# mainboard.net
KiCad netlist of a schematic drawn in EAGLE
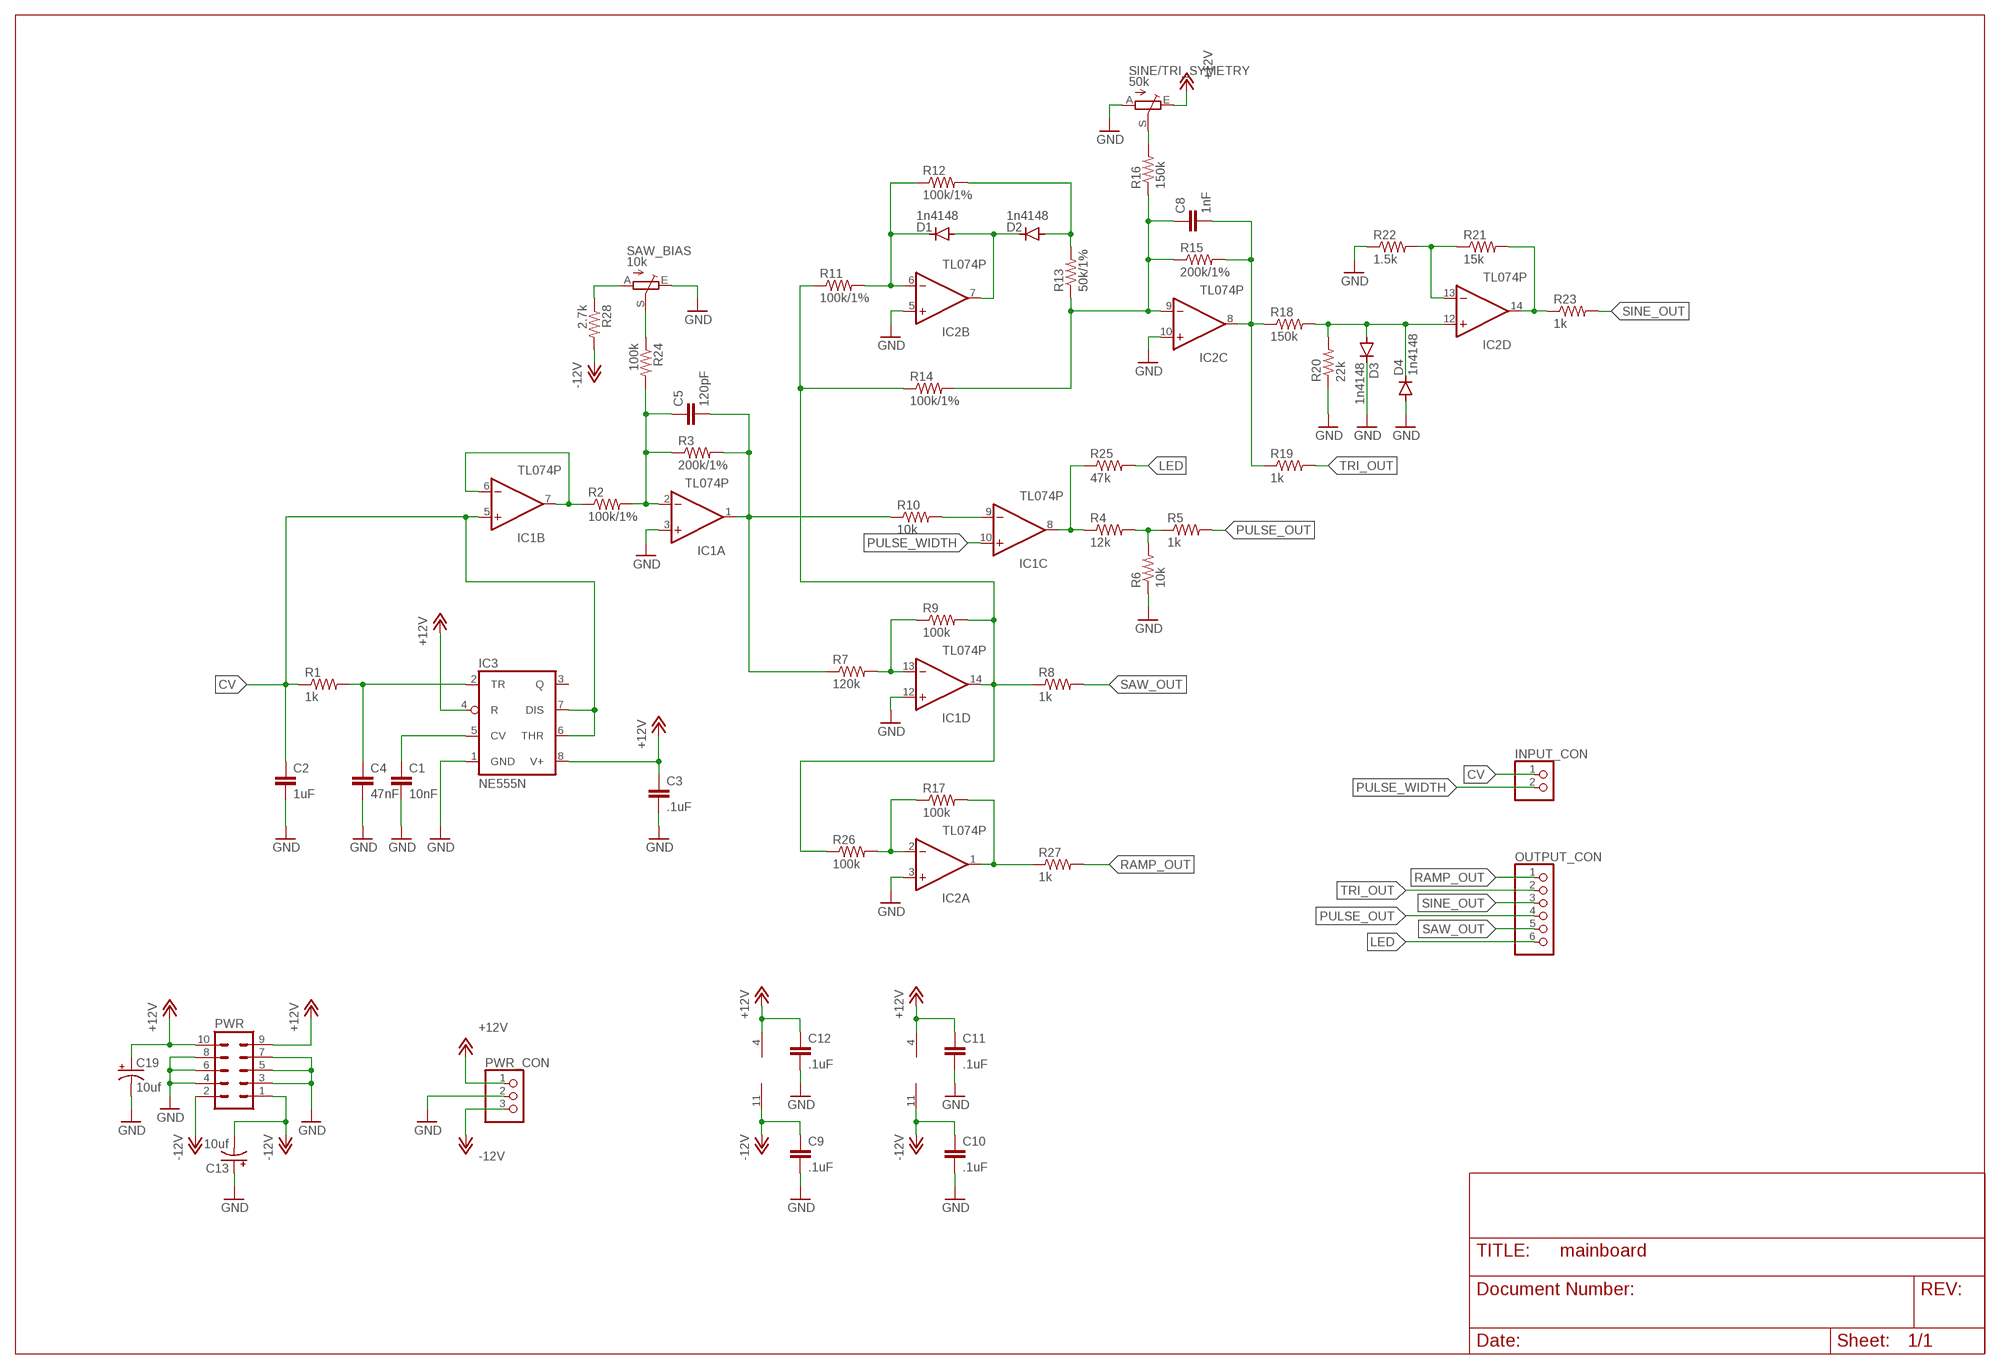
[diagram p0: schematic, sheet 1]

(export (version "E")
  (design (tool "Eeschema 10.0.6"))
  (components
    (comp (ref "C1")
      (value "10nF")
      (footprint "eagle-import:C050-024X044")
      (libsource (lib "eagle-import") (part "C-EU050-024X044"))
    )
    (comp (ref "C2")
      (value "1uF")
      (footprint "eagle-import:C075-032X103")
      (libsource (lib "eagle-import") (part "C-EU075-032X103"))
    )
    (comp (ref "C3")
      (value ".1uF")
      (footprint "eagle-import:C050-024X044")
      (libsource (lib "eagle-import") (part "C-EU050-024X044"))
    )
    (comp (ref "C4")
      (value "47nF")
      (footprint "eagle-import:C050-024X044")
      (libsource (lib "eagle-import") (part "C-EU050-024X044"))
    )
    (comp (ref "C5")
      (value "120pF")
      (footprint "eagle-import:C050-024X044")
      (libsource (lib "eagle-import") (part "C-EU050-024X044"))
    )
    (comp (ref "C8")
      (value "1nF")
      (footprint "eagle-import:C050-024X044")
      (libsource (lib "eagle-import") (part "C-EU050-024X044"))
    )
    (comp (ref "C9")
      (value ".1uF")
      (footprint "eagle-import:C050-024X044")
      (libsource (lib "eagle-import") (part "C-EU050-024X044"))
    )
    (comp (ref "C10")
      (value ".1uF")
      (footprint "eagle-import:C050-024X044")
      (libsource (lib "eagle-import") (part "C-EU050-024X044"))
    )
    (comp (ref "C11")
      (value ".1uF")
      (footprint "eagle-import:C050-024X044")
      (libsource (lib "eagle-import") (part "C-EU050-024X044"))
    )
    (comp (ref "C12")
      (value ".1uF")
      (footprint "eagle-import:C050-024X044")
      (libsource (lib "eagle-import") (part "C-EU050-024X044"))
    )
    (comp (ref "C13")
      (value "10uf")
      (footprint "eagle-import:E2,5-5")
      (libsource (lib "eagle-import") (part "CPOL-USE2.5-5"))
    )
    (comp (ref "C19")
      (value "10uf")
      (footprint "eagle-import:E2,5-5")
      (libsource (lib "eagle-import") (part "CPOL-USE2.5-5"))
    )
    (comp (ref "D1")
      (value "1n4148")
      (footprint "eagle-import:DO35-7")
      (libsource (lib "eagle-import") (part "1N4148DO35-7"))
    )
    (comp (ref "D2")
      (value "1n4148")
      (footprint "eagle-import:DO35-7")
      (libsource (lib "eagle-import") (part "1N4148DO35-7"))
    )
    (comp (ref "D3")
      (value "1n4148")
      (footprint "eagle-import:DO35-7")
      (libsource (lib "eagle-import") (part "1N4148DO35-7"))
    )
    (comp (ref "D4")
      (value "1n4148")
      (footprint "eagle-import:DO35-7")
      (libsource (lib "eagle-import") (part "1N4148DO35-7"))
    )
    (comp (ref "IC1")
      (value "TL074P")
      (footprint "eagle-import:DIL14")
      (libsource (lib "eagle-import") (part "TL074P"))
    )
    (comp (ref "IC2")
      (value "TL074P")
      (footprint "eagle-import:DIL14")
      (libsource (lib "eagle-import") (part "TL074P"))
    )
    (comp (ref "IC3")
      (value "NE555N")
      (footprint "eagle-import:DIL08")
      (libsource (lib "eagle-import") (part "555NNE"))
    )
    (comp (ref "INPUT_CON")
      (value "PINHD-1X2")
      (footprint "eagle-import:1X02")
      (libsource (lib "eagle-import") (part "PINHD-1X2"))
    )
    (comp (ref "OUTPUT_CON")
      (value "PINHD-1X6")
      (footprint "eagle-import:1X06")
      (libsource (lib "eagle-import") (part "PINHD-1X6"))
    )
    (comp (ref "PWR")
      (value "ML10")
      (footprint "eagle-import:ML10")
      (libsource (lib "eagle-import") (part "ML10"))
    )
    (comp (ref "PWR_CON")
      (value "PINHD-1X3")
      (footprint "eagle-import:1X03")
      (libsource (lib "eagle-import") (part "PINHD-1X3"))
    )
    (comp (ref "R1")
      (value "1k")
      (footprint "eagle-import:0207_7")
      (libsource (lib "eagle-import") (part "R-US_0207/7"))
    )
    (comp (ref "R2")
      (value "100k/1%")
      (footprint "eagle-import:0207_7")
      (libsource (lib "eagle-import") (part "R-US_0207/7"))
    )
    (comp (ref "R3")
      (value "200k/1%")
      (footprint "eagle-import:0207_7")
      (libsource (lib "eagle-import") (part "R-US_0207/7"))
    )
    (comp (ref "R4")
      (value "12k")
      (footprint "eagle-import:0207_7")
      (libsource (lib "eagle-import") (part "R-US_0207/7"))
    )
    (comp (ref "R5")
      (value "1k")
      (footprint "eagle-import:0207_7")
      (libsource (lib "eagle-import") (part "R-US_0207/7"))
    )
    (comp (ref "R6")
      (value "10k")
      (footprint "eagle-import:0207_7")
      (libsource (lib "eagle-import") (part "R-US_0207/7"))
    )
    (comp (ref "R7")
      (value "120k")
      (footprint "eagle-import:0207_7")
      (libsource (lib "eagle-import") (part "R-US_0207/7"))
    )
    (comp (ref "R8")
      (value "1k")
      (footprint "eagle-import:0207_7")
      (libsource (lib "eagle-import") (part "R-US_0207/7"))
    )
    (comp (ref "R9")
      (value "100k")
      (footprint "eagle-import:0207_7")
      (libsource (lib "eagle-import") (part "R-US_0207/7"))
    )
    (comp (ref "R10")
      (value "10k")
      (footprint "eagle-import:0207_7")
      (libsource (lib "eagle-import") (part "R-US_0207/7"))
    )
    (comp (ref "R11")
      (value "100k/1%")
      (footprint "eagle-import:0207_7")
      (libsource (lib "eagle-import") (part "R-US_0207/7"))
    )
    (comp (ref "R12")
      (value "100k/1%")
      (footprint "eagle-import:0207_7")
      (libsource (lib "eagle-import") (part "R-US_0207/7"))
    )
    (comp (ref "R13")
      (value "50k/1%")
      (footprint "eagle-import:0207_7")
      (libsource (lib "eagle-import") (part "R-US_0207/7"))
    )
    (comp (ref "R14")
      (value "100k/1%")
      (footprint "eagle-import:0207_7")
      (libsource (lib "eagle-import") (part "R-US_0207/7"))
    )
    (comp (ref "R15")
      (value "200k/1%")
      (footprint "eagle-import:0207_7")
      (libsource (lib "eagle-import") (part "R-US_0207/7"))
    )
    (comp (ref "R16")
      (value "150k")
      (footprint "eagle-import:0207_7")
      (libsource (lib "eagle-import") (part "R-US_0207/7"))
    )
    (comp (ref "R17")
      (value "100k")
      (footprint "eagle-import:0207_7")
      (libsource (lib "eagle-import") (part "R-US_0207/7"))
    )
    (comp (ref "R18")
      (value "150k")
      (footprint "eagle-import:0207_7")
      (libsource (lib "eagle-import") (part "R-US_0207/7"))
    )
    (comp (ref "R19")
      (value "1k")
      (footprint "eagle-import:0207_7")
      (libsource (lib "eagle-import") (part "R-US_0207/7"))
    )
    (comp (ref "R20")
      (value "22k")
      (footprint "eagle-import:0207_7")
      (libsource (lib "eagle-import") (part "R-US_0207/7"))
    )
    (comp (ref "R21")
      (value "15k")
      (footprint "eagle-import:0207_7")
      (libsource (lib "eagle-import") (part "R-US_0207/7"))
    )
    (comp (ref "R22")
      (value "1.5k")
      (footprint "eagle-import:0207_7")
      (libsource (lib "eagle-import") (part "R-US_0207/7"))
    )
    (comp (ref "R23")
      (value "1k")
      (footprint "eagle-import:0207_7")
      (libsource (lib "eagle-import") (part "R-US_0207/7"))
    )
    (comp (ref "R24")
      (value "100k")
      (footprint "eagle-import:0207_7")
      (libsource (lib "eagle-import") (part "R-US_0207/7"))
    )
    (comp (ref "R25")
      (value "47k")
      (footprint "eagle-import:0207_7")
      (libsource (lib "eagle-import") (part "R-US_0207/7"))
    )
    (comp (ref "R26")
      (value "100k")
      (footprint "eagle-import:0207_7")
      (libsource (lib "eagle-import") (part "R-US_0207/7"))
    )
    (comp (ref "R27")
      (value "1k")
      (footprint "eagle-import:0207_7")
      (libsource (lib "eagle-import") (part "R-US_0207/7"))
    )
    (comp (ref "R28")
      (value "2.7k")
      (footprint "eagle-import:0207_7")
      (libsource (lib "eagle-import") (part "R-US_0207/7"))
    )
    (comp (ref "SAW_BIAS")
      (value "10k")
      (footprint "eagle-import:S64YW")
      (libsource (lib "eagle-import") (part "TRIM_1234-S64YW"))
    )
    (comp (ref "SINE/TRI_SYMETRY")
      (value "50k")
      (footprint "eagle-import:S64YW")
      (libsource (lib "eagle-import") (part "TRIM_1234-S64YW"))
    )
  )
  (nets
    (net (code "1") (name "+12V") (class "Default")
      (node (ref "C11") (pin "1") (pinfunction "1_1") (pintype "passive"))
      (node (ref "C12") (pin "1") (pinfunction "1_1") (pintype "passive"))
      (node (ref "C19") (pin "+") (pinfunction "+_+") (pintype "passive"))
      (node (ref "C3") (pin "1") (pinfunction "1_1") (pintype "passive"))
      (node (ref "IC1") (pin "4") (pinfunction "V+_4") (pintype "power_in"))
      (node (ref "IC2") (pin "4") (pinfunction "V+_4") (pintype "power_in"))
      (node (ref "IC3") (pin "4") (pinfunction "R_4") (pintype "input"))
      (node (ref "IC3") (pin "8") (pinfunction "V+_8") (pintype "power_in"))
      (node (ref "PWR") (pin "10") (pinfunction "10_10") (pintype "passive"))
      (node (ref "PWR") (pin "9") (pinfunction "9_9") (pintype "passive"))
      (node (ref "PWR_CON") (pin "1") (pinfunction "1_1") (pintype "passive"))
      (node (ref "SINE/TRI_SYMETRY") (pin "E") (pinfunction "E_E") (pintype "passive"))
    )
    (net (code "2") (name "-12V") (class "Default")
      (node (ref "C10") (pin "1") (pinfunction "1_1") (pintype "passive"))
      (node (ref "C13") (pin "-") (pinfunction "-_-") (pintype "passive"))
      (node (ref "C9") (pin "1") (pinfunction "1_1") (pintype "passive"))
      (node (ref "IC1") (pin "11") (pinfunction "V-_11") (pintype "power_in"))
      (node (ref "IC2") (pin "11") (pinfunction "V-_11") (pintype "power_in"))
      (node (ref "PWR") (pin "1") (pinfunction "1_1") (pintype "passive"))
      (node (ref "PWR") (pin "2") (pinfunction "2_2") (pintype "passive"))
      (node (ref "PWR_CON") (pin "3") (pinfunction "3_3") (pintype "passive"))
      (node (ref "R28") (pin "2") (pinfunction "2_2") (pintype "passive"))
    )
    (net (code "3") (name "CV") (class "Default")
      (node (ref "C2") (pin "1") (pinfunction "1_1") (pintype "passive"))
      (node (ref "IC1") (pin "5") (pinfunction "+IN_5") (pintype "input"))
      (node (ref "IC3") (pin "6") (pinfunction "THR_6") (pintype "input"))
      (node (ref "IC3") (pin "7") (pinfunction "DIS_7") (pintype "input"))
      (node (ref "INPUT_CON") (pin "1") (pinfunction "1_1") (pintype "passive"))
      (node (ref "R1") (pin "1") (pinfunction "1_1") (pintype "passive"))
    )
    (net (code "4") (name "GND") (class "Default")
      (node (ref "C1") (pin "2") (pinfunction "2_2") (pintype "passive"))
      (node (ref "C10") (pin "2") (pinfunction "2_2") (pintype "passive"))
      (node (ref "C11") (pin "2") (pinfunction "2_2") (pintype "passive"))
      (node (ref "C12") (pin "2") (pinfunction "2_2") (pintype "passive"))
      (node (ref "C13") (pin "+") (pinfunction "+_+") (pintype "passive"))
      (node (ref "C19") (pin "-") (pinfunction "-_-") (pintype "passive"))
      (node (ref "C2") (pin "2") (pinfunction "2_2") (pintype "passive"))
      (node (ref "C3") (pin "2") (pinfunction "2_2") (pintype "passive"))
      (node (ref "C4") (pin "2") (pinfunction "2_2") (pintype "passive"))
      (node (ref "C9") (pin "2") (pinfunction "2_2") (pintype "passive"))
      (node (ref "D3") (pin "C") (pinfunction "C_C") (pintype "passive"))
      (node (ref "D4") (pin "A") (pinfunction "A_A") (pintype "passive"))
      (node (ref "IC1") (pin "12") (pinfunction "+IN_12") (pintype "input"))
      (node (ref "IC1") (pin "3") (pinfunction "+IN_3") (pintype "input"))
      (node (ref "IC2") (pin "10") (pinfunction "+IN_10") (pintype "input"))
      (node (ref "IC2") (pin "3") (pinfunction "+IN_3") (pintype "input"))
      (node (ref "IC2") (pin "5") (pinfunction "+IN_5") (pintype "input"))
      (node (ref "IC3") (pin "1") (pinfunction "GND_1") (pintype "power_in"))
      (node (ref "PWR") (pin "3") (pinfunction "3_3") (pintype "passive"))
      (node (ref "PWR") (pin "4") (pinfunction "4_4") (pintype "passive"))
      (node (ref "PWR") (pin "5") (pinfunction "5_5") (pintype "passive"))
      (node (ref "PWR") (pin "6") (pinfunction "6_6") (pintype "passive"))
      (node (ref "PWR") (pin "7") (pinfunction "7_7") (pintype "passive"))
      (node (ref "PWR") (pin "8") (pinfunction "8_8") (pintype "passive"))
      (node (ref "PWR_CON") (pin "2") (pinfunction "2_2") (pintype "passive"))
      (node (ref "R20") (pin "1") (pinfunction "1_1") (pintype "passive"))
      (node (ref "R22") (pin "1") (pinfunction "1_1") (pintype "passive"))
      (node (ref "R6") (pin "1") (pinfunction "1_1") (pintype "passive"))
      (node (ref "SAW_BIAS") (pin "E") (pinfunction "E_E") (pintype "passive"))
      (node (ref "SINE/TRI_SYMETRY") (pin "A") (pinfunction "A_A") (pintype "passive"))
    )
    (net (code "5") (name "LED") (class "Default")
      (node (ref "OUTPUT_CON") (pin "6") (pinfunction "6_6") (pintype "passive"))
      (node (ref "R25") (pin "2") (pinfunction "2_2") (pintype "passive"))
    )
    (net (code "6") (name "Net-(D2-PadA)") (class "Default")
      (node (ref "D2") (pin "A") (pinfunction "A_A") (pintype "passive"))
      (node (ref "R12") (pin "2") (pinfunction "2_2") (pintype "passive"))
      (node (ref "R13") (pin "2") (pinfunction "2_2") (pintype "passive"))
    )
    (net (code "7") (name "Net-(IC1A--IN)") (class "Default")
      (node (ref "C5") (pin "1") (pinfunction "1_1") (pintype "passive"))
      (node (ref "IC1") (pin "2") (pinfunction "-IN_2") (pintype "input"))
      (node (ref "R2") (pin "2") (pinfunction "2_2") (pintype "passive"))
      (node (ref "R24") (pin "2") (pinfunction "2_2") (pintype "passive"))
      (node (ref "R3") (pin "1") (pinfunction "1_1") (pintype "passive"))
    )
    (net (code "8") (name "Net-(IC1A-OUT)") (class "Default")
      (node (ref "C5") (pin "2") (pinfunction "2_2") (pintype "passive"))
      (node (ref "IC1") (pin "1") (pinfunction "OUT_1") (pintype "output"))
      (node (ref "R10") (pin "1") (pinfunction "1_1") (pintype "passive"))
      (node (ref "R3") (pin "2") (pinfunction "2_2") (pintype "passive"))
      (node (ref "R7") (pin "1") (pinfunction "1_1") (pintype "passive"))
    )
    (net (code "9") (name "Net-(IC1B--IN)") (class "Default")
      (node (ref "IC1") (pin "6") (pinfunction "-IN_6") (pintype "input"))
      (node (ref "IC1") (pin "7") (pinfunction "OUT_7") (pintype "output"))
      (node (ref "R2") (pin "1") (pinfunction "1_1") (pintype "passive"))
    )
    (net (code "10") (name "Net-(IC1C--IN)") (class "Default")
      (node (ref "IC1") (pin "9") (pinfunction "-IN_9") (pintype "input"))
      (node (ref "R10") (pin "2") (pinfunction "2_2") (pintype "passive"))
    )
    (net (code "11") (name "Net-(IC1C-OUT)") (class "Default")
      (node (ref "IC1") (pin "8") (pinfunction "OUT_8") (pintype "output"))
      (node (ref "R25") (pin "1") (pinfunction "1_1") (pintype "passive"))
      (node (ref "R4") (pin "1") (pinfunction "1_1") (pintype "passive"))
    )
    (net (code "12") (name "Net-(IC1D--IN)") (class "Default")
      (node (ref "IC1") (pin "13") (pinfunction "-IN_13") (pintype "input"))
      (node (ref "R7") (pin "2") (pinfunction "2_2") (pintype "passive"))
      (node (ref "R9") (pin "1") (pinfunction "1_1") (pintype "passive"))
    )
    (net (code "13") (name "Net-(IC1D-OUT)") (class "Default")
      (node (ref "IC1") (pin "14") (pinfunction "OUT_14") (pintype "output"))
      (node (ref "R11") (pin "1") (pinfunction "1_1") (pintype "passive"))
      (node (ref "R14") (pin "1") (pinfunction "1_1") (pintype "passive"))
      (node (ref "R26") (pin "1") (pinfunction "1_1") (pintype "passive"))
      (node (ref "R8") (pin "1") (pinfunction "1_1") (pintype "passive"))
      (node (ref "R9") (pin "2") (pinfunction "2_2") (pintype "passive"))
    )
    (net (code "14") (name "Net-(IC2A--IN)") (class "Default")
      (node (ref "IC2") (pin "2") (pinfunction "-IN_2") (pintype "input"))
      (node (ref "R17") (pin "1") (pinfunction "1_1") (pintype "passive"))
      (node (ref "R26") (pin "2") (pinfunction "2_2") (pintype "passive"))
    )
    (net (code "15") (name "Net-(IC2A-OUT)") (class "Default")
      (node (ref "IC2") (pin "1") (pinfunction "OUT_1") (pintype "output"))
      (node (ref "R17") (pin "2") (pinfunction "2_2") (pintype "passive"))
      (node (ref "R27") (pin "1") (pinfunction "1_1") (pintype "passive"))
    )
    (net (code "16") (name "Net-(IC2B--IN)") (class "Default")
      (node (ref "D1") (pin "C") (pinfunction "C_C") (pintype "passive"))
      (node (ref "IC2") (pin "6") (pinfunction "-IN_6") (pintype "input"))
      (node (ref "R11") (pin "2") (pinfunction "2_2") (pintype "passive"))
      (node (ref "R12") (pin "1") (pinfunction "1_1") (pintype "passive"))
    )
    (net (code "17") (name "Net-(IC2B-OUT)") (class "Default")
      (node (ref "D1") (pin "A") (pinfunction "A_A") (pintype "passive"))
      (node (ref "D2") (pin "C") (pinfunction "C_C") (pintype "passive"))
      (node (ref "IC2") (pin "7") (pinfunction "OUT_7") (pintype "output"))
    )
    (net (code "18") (name "Net-(IC2C--IN)") (class "Default")
      (node (ref "C8") (pin "1") (pinfunction "1_1") (pintype "passive"))
      (node (ref "IC2") (pin "9") (pinfunction "-IN_9") (pintype "input"))
      (node (ref "R13") (pin "1") (pinfunction "1_1") (pintype "passive"))
      (node (ref "R14") (pin "2") (pinfunction "2_2") (pintype "passive"))
      (node (ref "R15") (pin "1") (pinfunction "1_1") (pintype "passive"))
      (node (ref "R16") (pin "1") (pinfunction "1_1") (pintype "passive"))
    )
    (net (code "19") (name "Net-(IC2C-OUT)") (class "Default")
      (node (ref "C8") (pin "2") (pinfunction "2_2") (pintype "passive"))
      (node (ref "IC2") (pin "8") (pinfunction "OUT_8") (pintype "output"))
      (node (ref "R15") (pin "2") (pinfunction "2_2") (pintype "passive"))
      (node (ref "R18") (pin "1") (pinfunction "1_1") (pintype "passive"))
      (node (ref "R19") (pin "1") (pinfunction "1_1") (pintype "passive"))
    )
    (net (code "20") (name "Net-(IC2D-+IN)") (class "Default")
      (node (ref "D3") (pin "A") (pinfunction "A_A") (pintype "passive"))
      (node (ref "D4") (pin "C") (pinfunction "C_C") (pintype "passive"))
      (node (ref "IC2") (pin "12") (pinfunction "+IN_12") (pintype "input"))
      (node (ref "R18") (pin "2") (pinfunction "2_2") (pintype "passive"))
      (node (ref "R20") (pin "2") (pinfunction "2_2") (pintype "passive"))
    )
    (net (code "21") (name "Net-(IC2D--IN)") (class "Default")
      (node (ref "IC2") (pin "13") (pinfunction "-IN_13") (pintype "input"))
      (node (ref "R21") (pin "1") (pinfunction "1_1") (pintype "passive"))
      (node (ref "R22") (pin "2") (pinfunction "2_2") (pintype "passive"))
    )
    (net (code "22") (name "Net-(IC2D-OUT)") (class "Default")
      (node (ref "IC2") (pin "14") (pinfunction "OUT_14") (pintype "output"))
      (node (ref "R21") (pin "2") (pinfunction "2_2") (pintype "passive"))
      (node (ref "R23") (pin "1") (pinfunction "1_1") (pintype "passive"))
    )
    (net (code "23") (name "Net-(IC3-CV)") (class "Default")
      (node (ref "C1") (pin "1") (pinfunction "1_1") (pintype "passive"))
      (node (ref "IC3") (pin "5") (pinfunction "CV_5") (pintype "input"))
    )
    (net (code "24") (name "Net-(IC3-TR)") (class "Default")
      (node (ref "C4") (pin "1") (pinfunction "1_1") (pintype "passive"))
      (node (ref "IC3") (pin "2") (pinfunction "TR_2") (pintype "input"))
      (node (ref "R1") (pin "2") (pinfunction "2_2") (pintype "passive"))
    )
    (net (code "25") (name "Net-(R4-Pad2)") (class "Default")
      (node (ref "R4") (pin "2") (pinfunction "2_2") (pintype "passive"))
      (node (ref "R5") (pin "1") (pinfunction "1_1") (pintype "passive"))
      (node (ref "R6") (pin "2") (pinfunction "2_2") (pintype "passive"))
    )
    (net (code "26") (name "Net-(R16-Pad2)") (class "Default")
      (node (ref "R16") (pin "2") (pinfunction "2_2") (pintype "passive"))
      (node (ref "SINE/TRI_SYMETRY") (pin "S") (pinfunction "S_S") (pintype "passive"))
    )
    (net (code "27") (name "Net-(R24-Pad1)") (class "Default")
      (node (ref "R24") (pin "1") (pinfunction "1_1") (pintype "passive"))
      (node (ref "SAW_BIAS") (pin "S") (pinfunction "S_S") (pintype "passive"))
    )
    (net (code "28") (name "Net-(R28-Pad1)") (class "Default")
      (node (ref "R28") (pin "1") (pinfunction "1_1") (pintype "passive"))
      (node (ref "SAW_BIAS") (pin "A") (pinfunction "A_A") (pintype "passive"))
    )
    (net (code "29") (name "PULSE_OUT") (class "Default")
      (node (ref "OUTPUT_CON") (pin "4") (pinfunction "4_4") (pintype "passive"))
      (node (ref "R5") (pin "2") (pinfunction "2_2") (pintype "passive"))
    )
    (net (code "30") (name "PULSE_WIDTH") (class "Default")
      (node (ref "IC1") (pin "10") (pinfunction "+IN_10") (pintype "input"))
      (node (ref "INPUT_CON") (pin "2") (pinfunction "2_2") (pintype "passive"))
    )
    (net (code "31") (name "RAMP_OUT") (class "Default")
      (node (ref "OUTPUT_CON") (pin "1") (pinfunction "1_1") (pintype "passive"))
      (node (ref "R27") (pin "2") (pinfunction "2_2") (pintype "passive"))
    )
    (net (code "32") (name "SAW_OUT") (class "Default")
      (node (ref "OUTPUT_CON") (pin "5") (pinfunction "5_5") (pintype "passive"))
      (node (ref "R8") (pin "2") (pinfunction "2_2") (pintype "passive"))
    )
    (net (code "33") (name "SINE_OUT") (class "Default")
      (node (ref "OUTPUT_CON") (pin "3") (pinfunction "3_3") (pintype "passive"))
      (node (ref "R23") (pin "2") (pinfunction "2_2") (pintype "passive"))
    )
    (net (code "34") (name "TRI_OUT") (class "Default")
      (node (ref "OUTPUT_CON") (pin "2") (pinfunction "2_2") (pintype "passive"))
      (node (ref "R19") (pin "2") (pinfunction "2_2") (pintype "passive"))
    )
    (net (code "35") (name "unconnected-(IC3-Q-Pad3)") (class "Default")
      (node (ref "IC3") (pin "3") (pinfunction "Q_3") (pintype "output"))
    )
    (net (code "36") (name "unconnected-(SAW_BIAS-S-PadS@1)") (class "Default")
      (node (ref "SAW_BIAS") (pin "S@1") (pinfunction "S_S@1") (pintype "passive"))
    )
    (net (code "37") (name "unconnected-(SINE/TRI_SYMETRY-S-PadS@1)") (class "Default")
      (node (ref "SINE/TRI_SYMETRY") (pin "S@1") (pinfunction "S_S@1") (pintype "passive"))
    )
  )
)
